# Frame2TTL_v3_0_0_Sensor.net
KiCad netlist of a schematic drawn in EAGLE
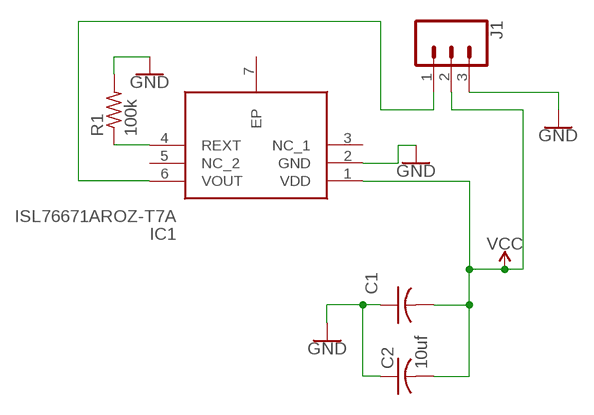
[diagram p0: schematic, sheet 1]

(export (version "E")
  (design (tool "Eeschema 10.0.6"))
  (components
    (comp (ref "C1")
      (value "0.1uf")
      (footprint "eagle-import:C0603K")
      (libsource (lib "eagle-import") (part "C-USC0603K"))
    )
    (comp (ref "C2")
      (value "10uf")
      (footprint "eagle-import:C0805K")
      (libsource (lib "eagle-import") (part "C-USC0805K"))
    )
    (comp (ref "IC1")
      (value "ISL76671AROZ-T7A")
      (footprint "eagle-import:SON65P210X200X80-7N")
      (fields (field (name "MOUSER_PART_NUMBER") "968-ISL76671AROZ-T7A"))
      (libsource (lib "eagle-import") (part "ISL76671AROZ-T7A"))
    )
    (comp (ref "J1")
      (value "CONN_03LOCK")
      (footprint "eagle-import:1X03_LOCK")
      (libsource (lib "eagle-import") (part "CONN_03LOCK"))
    )
    (comp (ref "R1")
      (value "100k")
      (footprint "eagle-import:R0805")
      (libsource (lib "eagle-import") (part "R-US_R0805"))
    )
  )
  (nets
    (net (code "1") (name "GND") (class "Default")
      (node (ref "C1") (pin "1") (pinfunction "1_1") (pintype "passive"))
      (node (ref "C2") (pin "1") (pinfunction "1_1") (pintype "passive"))
      (node (ref "IC1") (pin "2") (pinfunction "GND_2") (pintype "bidirectional"))
      (node (ref "J1") (pin "3") (pinfunction "3_3") (pintype "passive"))
      (node (ref "R1") (pin "2") (pinfunction "2_2") (pintype "passive"))
    )
    (net (code "2") (name "Net-(IC1-REXT)") (class "Default")
      (node (ref "IC1") (pin "4") (pinfunction "REXT_4") (pintype "bidirectional"))
      (node (ref "R1") (pin "1") (pinfunction "1_1") (pintype "passive"))
    )
    (net (code "3") (name "Net-(IC1-VOUT)") (class "Default")
      (node (ref "IC1") (pin "6") (pinfunction "VOUT_6") (pintype "bidirectional"))
      (node (ref "J1") (pin "1") (pinfunction "1_1") (pintype "passive"))
    )
    (net (code "4") (name "VCC") (class "Default")
      (node (ref "C1") (pin "2") (pinfunction "2_2") (pintype "passive"))
      (node (ref "C2") (pin "2") (pinfunction "2_2") (pintype "passive"))
      (node (ref "IC1") (pin "1") (pinfunction "VDD_1") (pintype "bidirectional"))
      (node (ref "J1") (pin "2") (pinfunction "2_2") (pintype "passive"))
    )
    (net (code "5") (name "unconnected-(IC1-EP-Pad7)") (class "Default")
      (node (ref "IC1") (pin "7") (pinfunction "EP_7") (pintype "bidirectional"))
    )
    (net (code "6") (name "unconnected-(IC1-NC_1-Pad3)") (class "Default")
      (node (ref "IC1") (pin "3") (pinfunction "NC_1_3") (pintype "bidirectional"))
    )
    (net (code "7") (name "unconnected-(IC1-NC_2-Pad5)") (class "Default")
      (node (ref "IC1") (pin "5") (pinfunction "NC_2_5") (pintype "bidirectional"))
    )
  )
)
